# Display_Port_Interface.net
KiCad netlist of a schematic drawn in Altium Designer
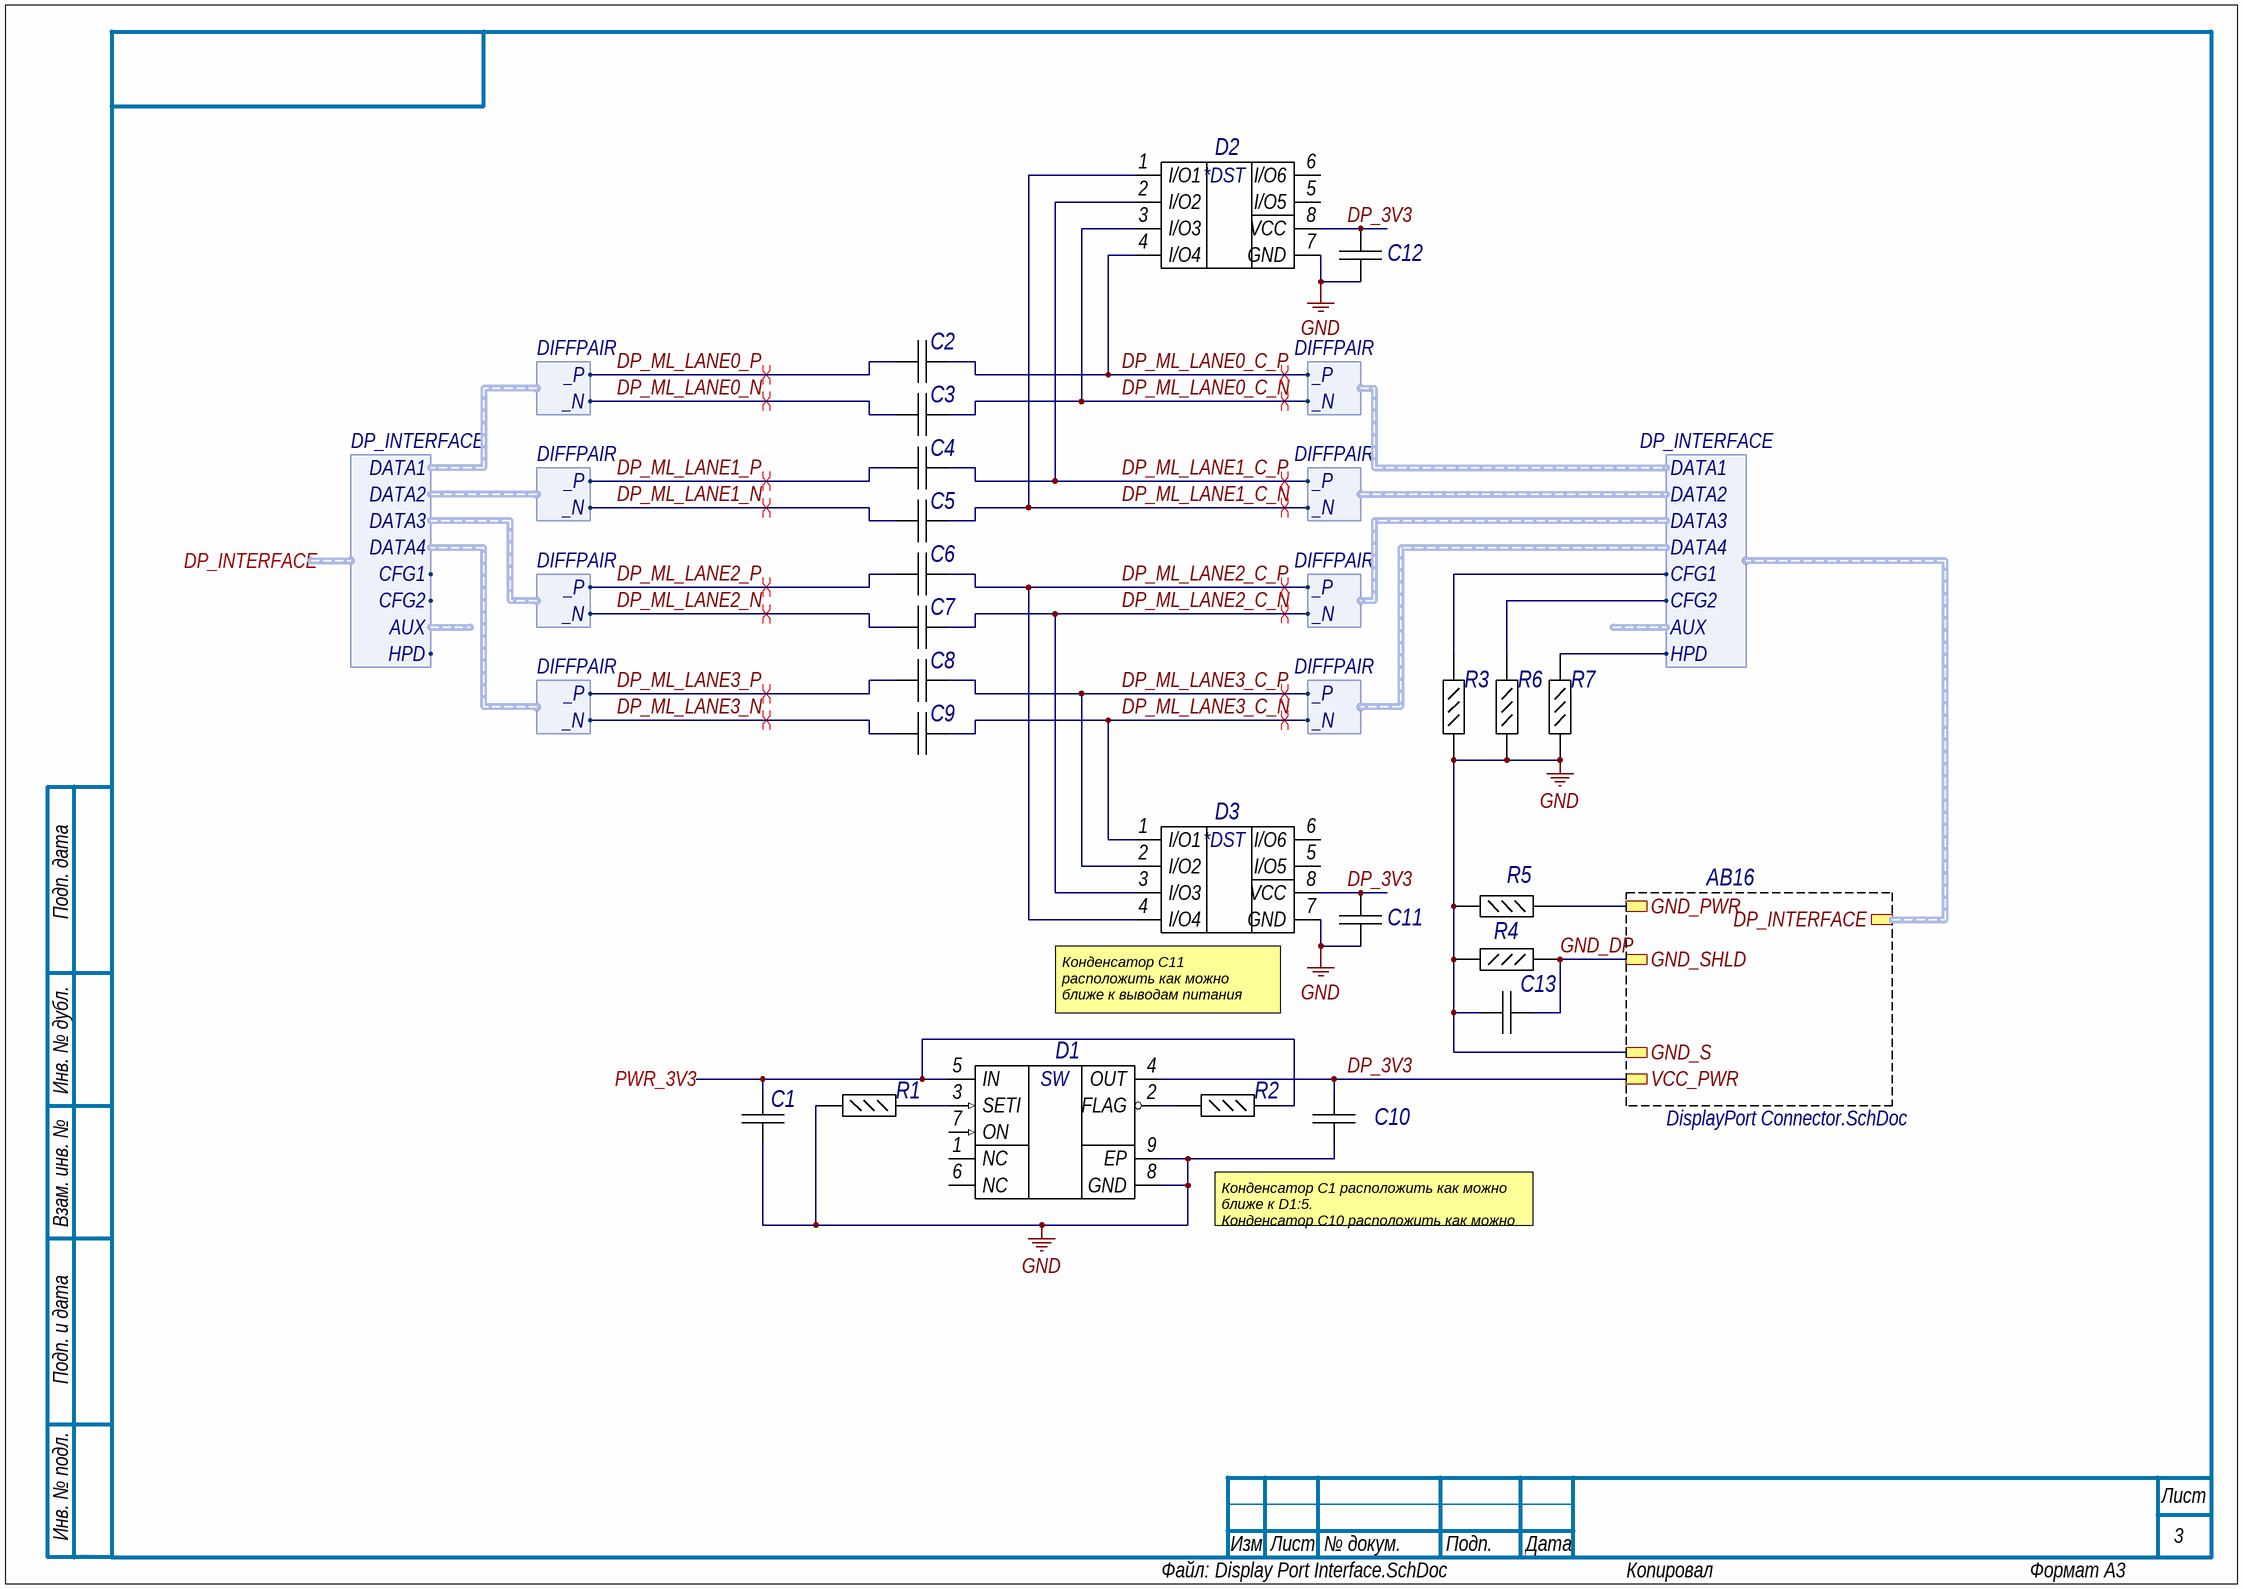
[diagram p0: Display Port Interface.SchDoc]

(export (version "E")
  (design (tool "Eeschema 10.0.6"))
  (components
    (comp (ref "C1")
      (value "GRM188R61A225KE34x")
      (footprint "CAPC1608X90X35ML10T15")
      (description "Chip Capacitor, 2.2 uF, +/- 10%, 10 V, -55 to 85 degC, 0603 (1608 Metric), RoHS, Tape and Reel")
      (fields (field (name "TOLERANCE") "10%"))
      (libsource (lib "MiniPC DB") (part "CAP_NP"))
    )
    (comp (ref "C2")
      (value "C1005X7R1E104M")
      (footprint "CAPC1005X55X10LL05")
      (description "Chip Capacitor, 0.1 uF, +/- 20%, 25 V, -55 to 125 degC, 0402 (1005 Metric), RoHS, Tape and Reel")
      (fields (field (name "TOLERANCE") "20%"))
      (libsource (lib "MiniPC DB") (part "CAP_NP"))
    )
    (comp (ref "C3")
      (value "C1005X7R1E104M")
      (footprint "CAPC1005X55X10LL05")
      (description "Chip Capacitor, 0.1 uF, +/- 20%, 25 V, -55 to 125 degC, 0402 (1005 Metric), RoHS, Tape and Reel")
      (fields (field (name "TOLERANCE") "20%"))
      (libsource (lib "MiniPC DB") (part "CAP_NP"))
    )
    (comp (ref "C4")
      (value "C1005X7R1E104M")
      (footprint "CAPC1005X55X10LL05")
      (description "Chip Capacitor, 0.1 uF, +/- 20%, 25 V, -55 to 125 degC, 0402 (1005 Metric), RoHS, Tape and Reel")
      (fields (field (name "TOLERANCE") "20%"))
      (libsource (lib "MiniPC DB") (part "CAP_NP"))
    )
    (comp (ref "C5")
      (value "C1005X7R1E104M")
      (footprint "CAPC1005X55X10LL05")
      (description "Chip Capacitor, 0.1 uF, +/- 20%, 25 V, -55 to 125 degC, 0402 (1005 Metric), RoHS, Tape and Reel")
      (fields (field (name "TOLERANCE") "20%"))
      (libsource (lib "MiniPC DB") (part "CAP_NP"))
    )
    (comp (ref "C6")
      (value "C1005X7R1E104M")
      (footprint "CAPC1005X55X10LL05")
      (description "Chip Capacitor, 0.1 uF, +/- 20%, 25 V, -55 to 125 degC, 0402 (1005 Metric), RoHS, Tape and Reel")
      (fields (field (name "TOLERANCE") "20%"))
      (libsource (lib "MiniPC DB") (part "CAP_NP"))
    )
    (comp (ref "C7")
      (value "C1005X7R1E104M")
      (footprint "CAPC1005X55X10LL05")
      (description "Chip Capacitor, 0.1 uF, +/- 20%, 25 V, -55 to 125 degC, 0402 (1005 Metric), RoHS, Tape and Reel")
      (fields (field (name "TOLERANCE") "20%"))
      (libsource (lib "MiniPC DB") (part "CAP_NP"))
    )
    (comp (ref "C8")
      (value "C1005X7R1E104M")
      (footprint "CAPC1005X55X10LL05")
      (description "Chip Capacitor, 0.1 uF, +/- 20%, 25 V, -55 to 125 degC, 0402 (1005 Metric), RoHS, Tape and Reel")
      (fields (field (name "TOLERANCE") "20%"))
      (libsource (lib "MiniPC DB") (part "CAP_NP"))
    )
    (comp (ref "C9")
      (value "C1005X7R1E104M")
      (footprint "CAPC1005X55X10LL05")
      (description "Chip Capacitor, 0.1 uF, +/- 20%, 25 V, -55 to 125 degC, 0402 (1005 Metric), RoHS, Tape and Reel")
      (fields (field (name "TOLERANCE") "20%"))
      (libsource (lib "MiniPC DB") (part "CAP_NP"))
    )
    (comp (ref "C10")
      (value "C1005X7R1E104M")
      (footprint "CAPC1005X55X10LL05")
      (description "Chip Capacitor, 0.1 uF, +/- 20%, 25 V, -55 to 125 degC, 0402 (1005 Metric), RoHS, Tape and Reel")
      (fields (field (name "TOLERANCE") "20%"))
      (libsource (lib "MiniPC DB") (part "CAP_NP"))
    )
    (comp (ref "C11")
      (value "C1005X7R1E104M")
      (footprint "CAPC1005X55X10LL05")
      (description "Chip Capacitor, 0.1 uF, +/- 20%, 25 V, -55 to 125 degC, 0402 (1005 Metric), RoHS, Tape and Reel")
      (fields (field (name "TOLERANCE") "20%"))
      (libsource (lib "MiniPC DB") (part "CAP_NP"))
    )
    (comp (ref "C12")
      (value "C1005X7R1E104M")
      (footprint "CAPC1005X55X10LL05")
      (description "Chip Capacitor, 0.1 uF, +/- 20%, 25 V, -55 to 125 degC, 0402 (1005 Metric), RoHS, Tape and Reel")
      (fields (field (name "TOLERANCE") "20%"))
      (libsource (lib "MiniPC DB") (part "CAP_NP"))
    )
    (comp (ref "C13")
      (value "GRM155R71H472KA01D")
      (footprint "CAPC1005X55X25NL05T10")
      (description "Chip Capacitor, 4.7 nF, +/- 10%, 50 V, -55 to 125 degC, 0402 (1005 Metric), RoHS, Tape and Reel")
      (fields (field (name "TOLERANCE") "10%") (field (name "MANUFACTURER") "Basic Passives"))
      (libsource (lib "MiniPC DB") (part "CAP_NP"))
    )
    (comp (ref "D1")
      (value "MAX14523AATA+")
      (footprint "MAXM-T833+2_V")
      (description "Adjustable Current-Limit Switch, 1.7 to 5.5 V, -40 to 125 degC, 8-Pin TDFN (T833+2), RoHS")
      (fields (field (name "MANUFACTURER") "Maxim"))
      (libsource (lib "MiniPC DB") (part "MAX14523A"))
    )
    (comp (ref "D2")
      (value "82401646")
      (footprint "MSOP-8L")
      (description "TVS Diode WE-TVS-SS, VRWM=5V")
      (fields (field (name "MANUFACTURER") "Wuerth Elektronik"))
      (libsource (lib "MiniPC DB") (part "82401646"))
    )
    (comp (ref "D3")
      (value "82401646")
      (footprint "MSOP-8L")
      (description "TVS Diode WE-TVS-SS, VRWM=5V")
      (fields (field (name "MANUFACTURER") "Wuerth Elektronik"))
      (libsource (lib "MiniPC DB") (part "82401646"))
    )
    (comp (ref "R1")
      (value "ERJ-2RKF2803X")
      (footprint "RESC1005X40X25LL05T05")
      (description "Chip Resistor, 280 KOhm, +/- 1%, 100 mW, -55 to 155 degC, 0402 (1005 Metric), RoHS, Cut Tape")
      (fields (field (name "TOLERANCE") "1%") (field (name "MANUFACTURER") "Basic Passives"))
      (libsource (lib "") (part "RES-0.05_2"))
    )
    (comp (ref "R2")
      (value "ERJ-2RKF1003X")
      (footprint "RESC1005X40X25LL05T05")
      (description "Chip Resistor, 100 KOhm, +/- 1%, 100 mW, -55 to 155 degC, 0402 (1005 Metric), RoHS, Tape and Reel")
      (fields (field (name "TOLERANCE") "1%") (field (name "MANUFACTURER") "Basic Passives"))
      (libsource (lib "") (part "RES-0.05_1"))
    )
    (comp (ref "R3")
      (value "ERJ-2RKF1004X")
      (footprint "RESC1005X40X25LL05T05")
      (description "Chip Resistor, 1 MOhm, +/- 1%, 100 mW, -55 to 155 degC, 0402 (1005 Metric), RoHS, Tape and Reel")
      (fields (field (name "TOLERANCE") "1%") (field (name "MANUFACTURER") "Basic Passives"))
      (libsource (lib "MiniPC DB") (part "RES-0.05"))
    )
    (comp (ref "R4")
      (value "ERJ-2RKF1004X")
      (footprint "RESC1005X40X25LL05T05")
      (description "Chip Resistor, 1 MOhm, +/- 1%, 100 mW, -55 to 155 degC, 0402 (1005 Metric), RoHS, Tape and Reel")
      (fields (field (name "TOLERANCE") "1%") (field (name "MANUFACTURER") "Basic Passives"))
      (libsource (lib "MiniPC DB") (part "RES-0.05"))
    )
    (comp (ref "R5")
      (value "ERJ-2GE0R00X")
      (footprint "RESC1005X40X25LL05T05")
      (description "Chip Resistor, 0 mOhm, +/- 5%, 100 mW, -55 to 155 degC, 0402 (1005 Metric), RoHS, Tape and Reel")
      (fields (field (name "TOLERANCE") "5%") (field (name "MANUFACTURER") "Basic Passives"))
      (libsource (lib "") (part "RES-0.05_1"))
    )
    (comp (ref "R6")
      (value "ERJ-2RKF1004X")
      (footprint "RESC1005X40X25LL05T05")
      (description "Chip Resistor, 1 MOhm, +/- 1%, 100 mW, -55 to 155 degC, 0402 (1005 Metric), RoHS, Tape and Reel")
      (fields (field (name "TOLERANCE") "1%") (field (name "MANUFACTURER") "Basic Passives"))
      (libsource (lib "MiniPC DB") (part "RES-0.05"))
    )
    (comp (ref "R7")
      (value "ERJ-2RKF1003X")
      (footprint "RESC1005X40X25LL05T05")
      (description "Chip Resistor, 100 KOhm, +/- 1%, 100 mW, -55 to 155 degC, 0402 (1005 Metric), RoHS, Tape and Reel")
      (fields (field (name "TOLERANCE") "1%") (field (name "MANUFACTURER") "Basic Passives"))
      (libsource (lib "MiniPC DB") (part "RES-0.05"))
    )
  )
  (nets
    (net (code "4") (name "/DP_3V3") (class "Default")
      (node (ref "C10") (pin "2") (pinfunction "2_2") (pintype "passive"))
      (node (ref "C11") (pin "2") (pinfunction "2_2") (pintype "passive"))
      (node (ref "C12") (pin "2") (pinfunction "2_2") (pintype "passive"))
      (node (ref "D1") (pin "4") (pinfunction "OUT_4") (pintype "power_in"))
      (node (ref "D2") (pin "8") (pinfunction "VCC_8") (pintype "passive"))
      (node (ref "D3") (pin "8") (pinfunction "VCC_8") (pintype "passive"))
    )
    (net (code "7") (name "/DP_ML_LANE0_C_N") (class "Default")
      (node (ref "C3") (pin "2") (pinfunction "2_2") (pintype "passive"))
      (node (ref "D2") (pin "3") (pinfunction "I/O3_3") (pintype "passive"))
    )
    (net (code "8") (name "/DP_ML_LANE0_C_P") (class "Default")
      (node (ref "C2") (pin "2") (pinfunction "2_2") (pintype "passive"))
      (node (ref "D2") (pin "4") (pinfunction "I/O4_4") (pintype "passive"))
    )
    (net (code "9") (name "/DP_ML_LANE0_N") (class "Default")
      (node (ref "C3") (pin "1") (pinfunction "1_1") (pintype "passive"))
    )
    (net (code "10") (name "/DP_ML_LANE0_P") (class "Default")
      (node (ref "C2") (pin "1") (pinfunction "1_1") (pintype "passive"))
    )
    (net (code "11") (name "/DP_ML_LANE1_C_N") (class "Default")
      (node (ref "C5") (pin "2") (pinfunction "2_2") (pintype "passive"))
      (node (ref "D2") (pin "1") (pinfunction "I/O1_1") (pintype "passive"))
    )
    (net (code "12") (name "/DP_ML_LANE1_C_P") (class "Default")
      (node (ref "C4") (pin "2") (pinfunction "2_2") (pintype "passive"))
      (node (ref "D2") (pin "2") (pinfunction "I/O2_2") (pintype "passive"))
    )
    (net (code "13") (name "/DP_ML_LANE1_N") (class "Default")
      (node (ref "C5") (pin "1") (pinfunction "1_1") (pintype "passive"))
    )
    (net (code "14") (name "/DP_ML_LANE1_P") (class "Default")
      (node (ref "C4") (pin "1") (pinfunction "1_1") (pintype "passive"))
    )
    (net (code "15") (name "/DP_ML_LANE2_C_N") (class "Default")
      (node (ref "C7") (pin "2") (pinfunction "2_2") (pintype "passive"))
      (node (ref "D3") (pin "3") (pinfunction "I/O3_3") (pintype "passive"))
    )
    (net (code "16") (name "/DP_ML_LANE2_C_P") (class "Default")
      (node (ref "C6") (pin "2") (pinfunction "2_2") (pintype "passive"))
      (node (ref "D3") (pin "4") (pinfunction "I/O4_4") (pintype "passive"))
    )
    (net (code "17") (name "/DP_ML_LANE2_N") (class "Default")
      (node (ref "C7") (pin "1") (pinfunction "1_1") (pintype "passive"))
    )
    (net (code "18") (name "/DP_ML_LANE2_P") (class "Default")
      (node (ref "C6") (pin "1") (pinfunction "1_1") (pintype "passive"))
    )
    (net (code "19") (name "/DP_ML_LANE3_C_N") (class "Default")
      (node (ref "C9") (pin "2") (pinfunction "2_2") (pintype "passive"))
      (node (ref "D3") (pin "1") (pinfunction "I/O1_1") (pintype "passive"))
    )
    (net (code "20") (name "/DP_ML_LANE3_C_P") (class "Default")
      (node (ref "C8") (pin "2") (pinfunction "2_2") (pintype "passive"))
      (node (ref "D3") (pin "2") (pinfunction "I/O2_2") (pintype "passive"))
    )
    (net (code "21") (name "/DP_ML_LANE3_N") (class "Default")
      (node (ref "C9") (pin "1") (pinfunction "1_1") (pintype "passive"))
    )
    (net (code "22") (name "/DP_ML_LANE3_P") (class "Default")
      (node (ref "C8") (pin "1") (pinfunction "1_1") (pintype "passive"))
    )
    (net (code "23") (name "/GND_DP") (class "Default")
      (node (ref "C13") (pin "2") (pinfunction "2_2") (pintype "passive"))
      (node (ref "R4") (pin "2") (pinfunction "2_2") (pintype "passive"))
    )
    (net (code "24") (name "/GND_PWR") (class "Default")
      (node (ref "R5") (pin "2") (pinfunction "2_2") (pintype "passive"))
    )
    (net (code "25") (name "/PWR_3V3") (class "Default")
      (node (ref "C1") (pin "1") (pinfunction "1_1") (pintype "passive"))
      (node (ref "D1") (pin "5") (pinfunction "IN_5") (pintype "power_in"))
      (node (ref "R2") (pin "2") (pinfunction "2_2") (pintype "passive"))
    )
    (net (code "28") (name "GND") (class "Default")
      (node (ref "C1") (pin "2") (pinfunction "2_2") (pintype "passive"))
      (node (ref "C10") (pin "1") (pinfunction "1_1") (pintype "passive"))
      (node (ref "C11") (pin "1") (pinfunction "1_1") (pintype "passive"))
      (node (ref "C12") (pin "1") (pinfunction "1_1") (pintype "passive"))
      (node (ref "C13") (pin "1") (pinfunction "1_1") (pintype "passive"))
      (node (ref "D1") (pin "8") (pinfunction "GND_8") (pintype "passive"))
      (node (ref "D1") (pin "9") (pinfunction "EP_9") (pintype "power_in"))
      (node (ref "D2") (pin "7") (pinfunction "GND_7") (pintype "passive"))
      (node (ref "D3") (pin "7") (pinfunction "GND_7") (pintype "passive"))
      (node (ref "R1") (pin "2") (pinfunction "2_2") (pintype "passive"))
      (node (ref "R3") (pin "1") (pinfunction "1_1") (pintype "passive"))
      (node (ref "R4") (pin "1") (pinfunction "1_1") (pintype "passive"))
      (node (ref "R5") (pin "1") (pinfunction "1_1") (pintype "passive"))
      (node (ref "R6") (pin "1") (pinfunction "1_1") (pintype "passive"))
      (node (ref "R7") (pin "1") (pinfunction "1_1") (pintype "passive"))
    )
    (net (code "29") (name "Net-(D1-FLAG)") (class "Default")
      (node (ref "D1") (pin "2") (pinfunction "FLAG_2") (pintype "open_collector"))
      (node (ref "R2") (pin "1") (pinfunction "1_1") (pintype "passive"))
    )
    (net (code "30") (name "Net-(D1-SETI)") (class "Default")
      (node (ref "D1") (pin "3") (pinfunction "SETI_3") (pintype "input"))
      (node (ref "R1") (pin "1") (pinfunction "1_1") (pintype "passive"))
    )
    (net (code "31") (name "unconnected-(D1-NC-Pad1)") (class "Default")
      (node (ref "D1") (pin "1") (pinfunction "NC_1") (pintype "passive"))
    )
    (net (code "32") (name "unconnected-(D1-NC-Pad6)") (class "Default")
      (node (ref "D1") (pin "6") (pinfunction "NC_6") (pintype "passive"))
    )
    (net (code "33") (name "unconnected-(D1-ON-Pad7)") (class "Default")
      (node (ref "D1") (pin "7") (pinfunction "ON_7") (pintype "input"))
    )
    (net (code "34") (name "unconnected-(D2-I{slash}O5-Pad5)") (class "Default")
      (node (ref "D2") (pin "5") (pinfunction "I/O5_5") (pintype "passive"))
    )
    (net (code "35") (name "unconnected-(D2-I{slash}O6-Pad6)") (class "Default")
      (node (ref "D2") (pin "6") (pinfunction "I/O6_6") (pintype "passive"))
    )
    (net (code "36") (name "unconnected-(D3-I{slash}O5-Pad5)") (class "Default")
      (node (ref "D3") (pin "5") (pinfunction "I/O5_5") (pintype "passive"))
    )
    (net (code "37") (name "unconnected-(D3-I{slash}O6-Pad6)") (class "Default")
      (node (ref "D3") (pin "6") (pinfunction "I/O6_6") (pintype "passive"))
    )
    (net (code "38") (name "unconnected-(R3-Pad2)") (class "Default")
      (node (ref "R3") (pin "2") (pinfunction "2_2") (pintype "passive"))
    )
    (net (code "39") (name "unconnected-(R6-Pad2)") (class "Default")
      (node (ref "R6") (pin "2") (pinfunction "2_2") (pintype "passive"))
    )
    (net (code "40") (name "unconnected-(R7-Pad2)") (class "Default")
      (node (ref "R7") (pin "2") (pinfunction "2_2") (pintype "passive"))
    )
  )
)
